# Watchdog.net
KiCad netlist of a schematic drawn in Altium Designer
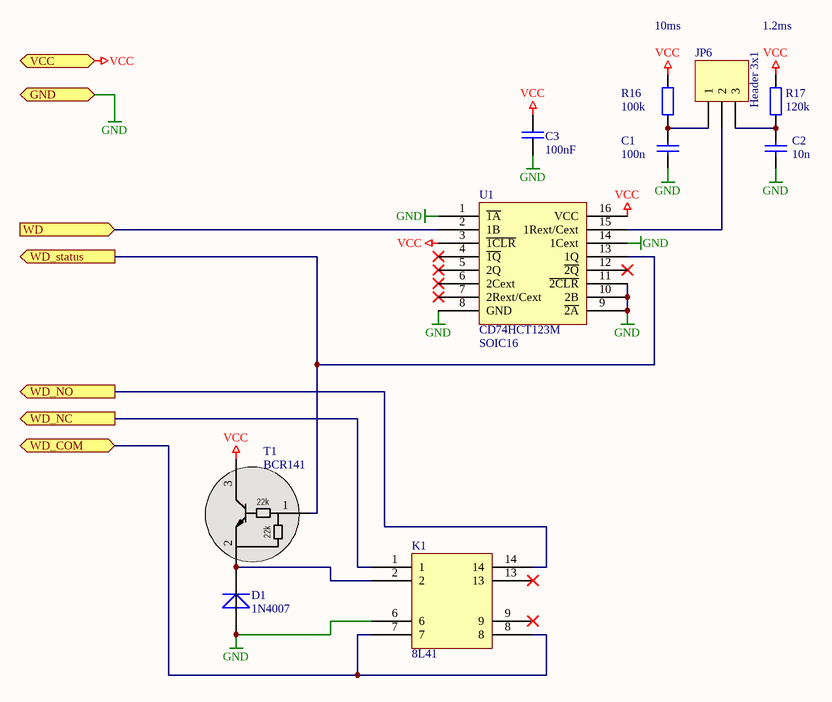
[diagram p0: Watchdog.SchDoc]

(export (version "E")
  (design (tool "Eeschema 10.0.6"))
  (components
    (comp (ref "C1")
      (value "100n")
      (footprint "0805")
      (description "Capacitor")
      (fields (field (name "#PUBLISHER") "Dr. A. Heinzelmann"))
      (libsource (lib "rc") (part "C"))
    )
    (comp (ref "C2")
      (value "10n")
      (footprint "0805")
      (description "Capacitor")
      (fields (field (name "#PUBLISHER") "Dr. A. Heinzelmann"))
      (libsource (lib "rc") (part "C"))
    )
    (comp (ref "C3")
      (value "100nF")
      (footprint "1206")
      (description "Capacitor")
      (fields (field (name "#PUBLISHER") "Dr. A. Heinzelmann"))
      (libsource (lib "mzueger") (part "C"))
    )
    (comp (ref "D1")
      (value "1N4007")
      (footprint "SMD-DO214AC")
      (description "High Conductance Fast Diode")
      (fields (field (name "#PUBLISHER") "Dr. A. Heinzelmann"))
      (libsource (lib "mzueger") (part "1N4148"))
    )
    (comp (ref "JP6")
      (value "Header 3x1")
      (footprint "Header - 1x3 - V")
      (description "Header, 3-Pin")
      (fields (field (name "PUBLISHER") "Altium Limited"))
      (libsource (lib "rc") (part "Header 3"))
    )
    (comp (ref "K1")
      (value "8L41")
      (footprint "8L41")
      (description "Reed Relais")
      (libsource (lib "Integrated_Library") (part "8L41"))
    )
    (comp (ref "R16")
      (value "100k")
      (footprint "0805")
      (description "Resistor")
      (fields (field (name "#PUBLISHER") "Dr. A. Heinzelmann"))
      (libsource (lib "rc") (part "R"))
    )
    (comp (ref "R17")
      (value "120k")
      (footprint "0805")
      (description "Resistor")
      (fields (field (name "#PUBLISHER") "Dr. A. Heinzelmann"))
      (libsource (lib "rc") (part "R"))
    )
    (comp (ref "T1")
      (value "BCR141")
      (footprint "SOT23-3Pin")
      (description "General Purpose NPN Transistor")
      (fields (field (name "MANUFACTURER") "Infineon") (field (name "TYPE") "BCR141"))
      (libsource (lib "mzueger") (part "BCR141"))
    )
    (comp (ref "U1")
      (value "CD74HCT123M")
      (footprint "SOIC16")
      (description "Multivibrator")
      (fields (field (name "TYPE") "CD74HCT123M"))
      (libsource (lib "mzueger") (part "CD74HCT123M"))
    )
  )
  (nets
    (net (code "1") (name "/WD") (class "Default")
      (node (ref "U1") (pin "2") (pinfunction "1B_2") (pintype "passive"))
    )
    (net (code "2") (name "/WD_COM") (class "Default")
      (node (ref "K1") (pin "7") (pinfunction "7_7") (pintype "passive"))
      (node (ref "K1") (pin "8") (pinfunction "8_8") (pintype "passive"))
    )
    (net (code "3") (name "/WD_NC") (class "Default")
      (node (ref "K1") (pin "1") (pinfunction "1_1") (pintype "passive"))
    )
    (net (code "4") (name "/WD_NO") (class "Default")
      (node (ref "K1") (pin "14") (pinfunction "14_14") (pintype "passive"))
    )
    (net (code "5") (name "/WD_status") (class "Default")
      (node (ref "T1") (pin "1") (pinfunction "B_1") (pintype "passive"))
      (node (ref "U1") (pin "13") (pinfunction "1Q_13") (pintype "passive"))
    )
    (net (code "6") (name "GND") (class "Default")
      (node (ref "C1") (pin "1") (pinfunction "1_1") (pintype "passive"))
      (node (ref "C2") (pin "1") (pinfunction "1_1") (pintype "passive"))
      (node (ref "C3") (pin "1") (pinfunction "1_1") (pintype "passive"))
      (node (ref "D1") (pin "2") (pinfunction "A_2") (pintype "passive"))
      (node (ref "K1") (pin "6") (pinfunction "6_6") (pintype "passive"))
      (node (ref "U1") (pin "1") (pinfunction "~{1A}_1") (pintype "passive"))
      (node (ref "U1") (pin "10") (pinfunction "2B_10") (pintype "passive"))
      (node (ref "U1") (pin "11") (pinfunction "~{2CLR}_11") (pintype "passive"))
      (node (ref "U1") (pin "14") (pinfunction "1Cext_14") (pintype "passive"))
      (node (ref "U1") (pin "8") (pinfunction "GND_8") (pintype "passive"))
      (node (ref "U1") (pin "9") (pinfunction "~{2A}_9") (pintype "passive"))
    )
    (net (code "7") (name "Net-(C1-Pad2)") (class "Default")
      (node (ref "C1") (pin "2") (pinfunction "2_2") (pintype "passive"))
      (node (ref "JP6") (pin "1") (pinfunction "1_1") (pintype "passive"))
      (node (ref "R16") (pin "1") (pinfunction "1_1") (pintype "passive"))
    )
    (net (code "8") (name "Net-(C2-Pad2)") (class "Default")
      (node (ref "C2") (pin "2") (pinfunction "2_2") (pintype "passive"))
      (node (ref "JP6") (pin "3") (pinfunction "3_3") (pintype "passive"))
      (node (ref "R17") (pin "1") (pinfunction "1_1") (pintype "passive"))
    )
    (net (code "9") (name "Net-(D1-K)") (class "Default")
      (node (ref "D1") (pin "1") (pinfunction "K_1") (pintype "passive"))
      (node (ref "K1") (pin "2") (pinfunction "2_2") (pintype "passive"))
      (node (ref "T1") (pin "2") (pinfunction "E_2") (pintype "passive"))
    )
    (net (code "10") (name "Net-(U1-1Rext{slash}Cext)") (class "Default")
      (node (ref "JP6") (pin "2") (pinfunction "2_2") (pintype "passive"))
      (node (ref "U1") (pin "15") (pinfunction "1Rext/Cext_15") (pintype "passive"))
    )
    (net (code "11") (name "VCC") (class "Default")
      (node (ref "C3") (pin "2") (pinfunction "2_2") (pintype "passive"))
      (node (ref "R16") (pin "2") (pinfunction "2_2") (pintype "passive"))
      (node (ref "R17") (pin "2") (pinfunction "2_2") (pintype "passive"))
      (node (ref "T1") (pin "3") (pinfunction "C_3") (pintype "passive"))
      (node (ref "U1") (pin "16") (pinfunction "VCC_16") (pintype "passive"))
      (node (ref "U1") (pin "3") (pinfunction "~{1CLR}_3") (pintype "passive"))
    )
    (net (code "12") (name "unconnected-(K1-Pad9)") (class "Default")
      (node (ref "K1") (pin "9") (pinfunction "9_9") (pintype "passive+no_connect"))
    )
    (net (code "13") (name "unconnected-(K1-Pad13)") (class "Default")
      (node (ref "K1") (pin "13") (pinfunction "13_13") (pintype "passive+no_connect"))
    )
    (net (code "14") (name "unconnected-(U1-2Cext-Pad6)") (class "Default")
      (node (ref "U1") (pin "6") (pinfunction "2Cext_6") (pintype "passive+no_connect"))
    )
    (net (code "15") (name "unconnected-(U1-2Q-Pad5)") (class "Default")
      (node (ref "U1") (pin "5") (pinfunction "2Q_5") (pintype "passive+no_connect"))
    )
    (net (code "16") (name "unconnected-(U1-2Rext{slash}Cext-Pad7)") (class "Default")
      (node (ref "U1") (pin "7") (pinfunction "2Rext/Cext_7") (pintype "passive+no_connect"))
    )
    (net (code "17") (name "unconnected-(U1-~{1Q}-Pad4)") (class "Default")
      (node (ref "U1") (pin "4") (pinfunction "~{1Q}_4") (pintype "passive+no_connect"))
    )
    (net (code "18") (name "unconnected-(U1-~{2Q}-Pad12)") (class "Default")
      (node (ref "U1") (pin "12") (pinfunction "~{2Q}_12") (pintype "passive+no_connect"))
    )
  )
)
